# V1_0.net
KiCad netlist of a schematic drawn in Altium Designer
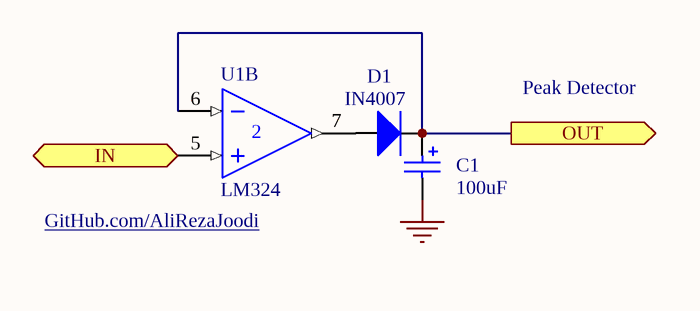
[diagram p0: V1.0.SchDoc]

(export (version "E")
  (design (tool "Eeschema 10.0.6"))
  (components
    (comp (ref "C1")
      (value "100uF")
      (footprint "CAPPR2.5-6.3x5")
      (description "Polarized Capacitor (Radial)")
      (fields (field (name "MANUFACTURER") "Generic Components") (field (name "PUBLISHER") "Altium Limited"))
      (libsource (lib "Miscellaneous Devices") (part "Cap Pol1"))
    )
    (comp (ref "D1")
      (value "IN4007")
      (footprint "DIODE-0.4")
      (description "Default Diode")
      (fields (field (name "MANUFACTURER") "Generic Components") (field (name "PUBLISHER") "Altium Limited"))
      (libsource (lib "Miscellaneous Devices") (part "Diode"))
    )
    (comp (ref "U1")
      (value "LM324")
      (footprint "646-06")
      (description "Quad Low-Power Operational Amplifier")
      (fields (field (name "PUBLISHER") "Altium Limited"))
      (libsource (lib "my Libraries") (part "LM324"))
    )
  )
  (nets
    (net (code "1") (name "/IN") (class "Default")
      (node (ref "U1") (pin "5") (pinfunction "IN+_5") (pintype "input"))
    )
    (net (code "2") (name "/OUT") (class "Default")
      (node (ref "C1") (pin "1") (pinfunction "1_1") (pintype "passive"))
      (node (ref "D1") (pin "2") (pinfunction "K_2") (pintype "passive"))
      (node (ref "U1") (pin "6") (pinfunction "IN-_6") (pintype "input"))
    )
    (net (code "3") (name "GND") (class "Default")
      (node (ref "C1") (pin "2") (pinfunction "2_2") (pintype "passive"))
    )
    (net (code "4") (name "Net-(D1-A)") (class "Default")
      (node (ref "D1") (pin "1") (pinfunction "A_1") (pintype "passive"))
      (node (ref "U1") (pin "7") (pinfunction "OUT_7") (pintype "output"))
    )
  )
)
